# Satellite_Transceiver_Breakout__Swarm_M1.net
KiCad netlist of a schematic drawn in EAGLE
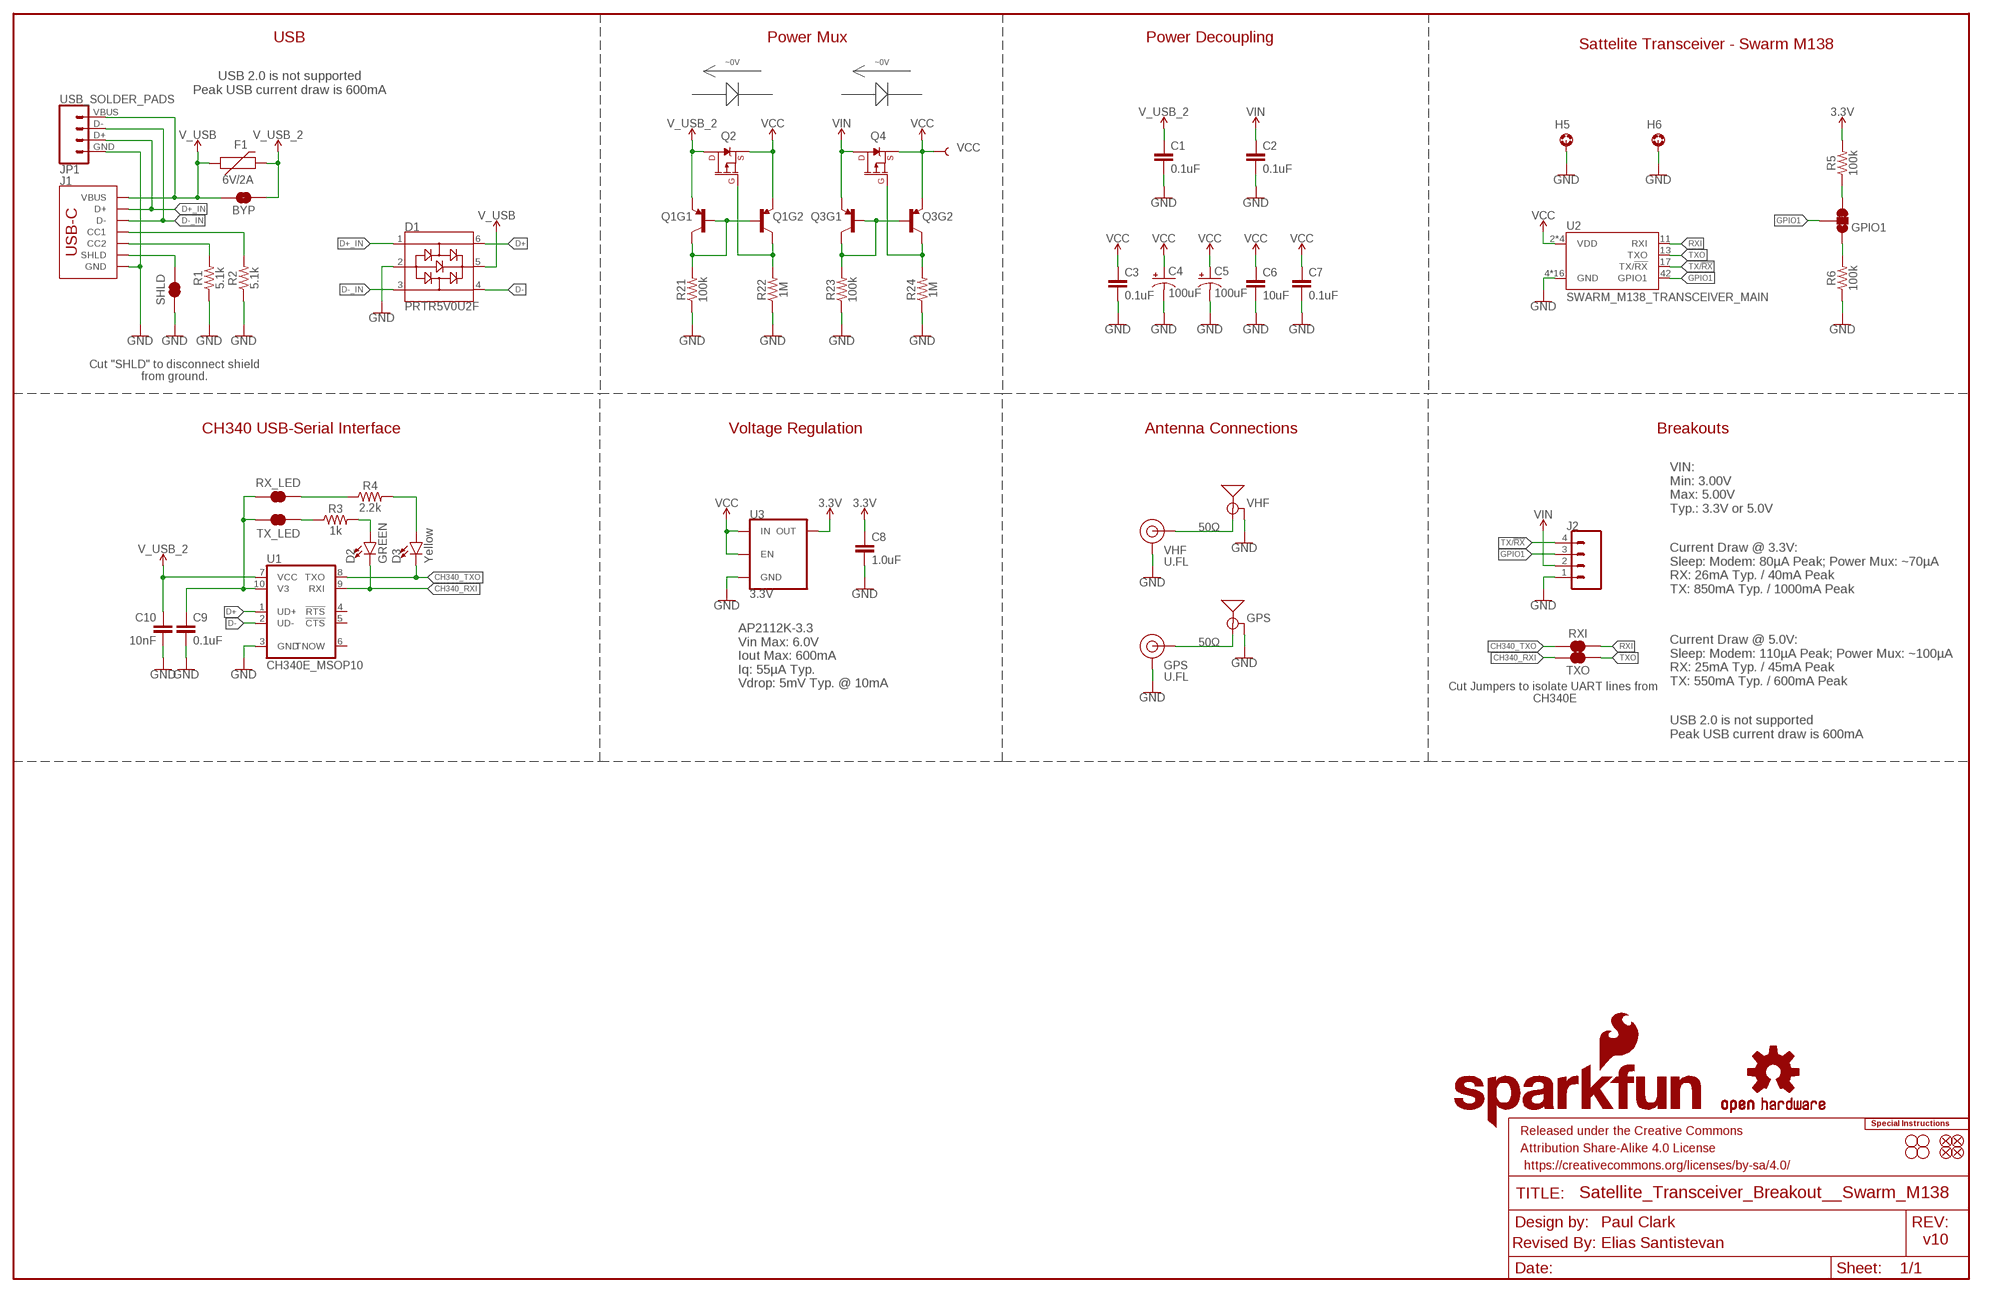
[diagram p0: schematic, sheet 1]

(export (version "E")
  (design (tool "Eeschema 10.0.6"))
  (components
    (comp (ref "BYP")
      (value "JUMPER-SMT_2_NO_SILK")
      (footprint "eagle-import:SMT-JUMPER_2_NO_SILK")
      (libsource (lib "eagle-import") (part "JUMPER-SMT_2_NO_SILK"))
    )
    (comp (ref "C1")
      (value "0.1uF")
      (footprint "eagle-import:0603")
      (libsource (lib "eagle-import") (part "0.1UF-0603-25V-5%"))
    )
    (comp (ref "C2")
      (value "0.1uF")
      (footprint "eagle-import:0603")
      (libsource (lib "eagle-import") (part "0.1UF-0603-25V-5%"))
    )
    (comp (ref "C3")
      (value "0.1uF")
      (footprint "eagle-import:0603")
      (libsource (lib "eagle-import") (part "0.1UF-0603-25V-5%"))
    )
    (comp (ref "C4")
      (value "100uF")
      (footprint "eagle-import:PANASONIC_D")
      (libsource (lib "eagle-import") (part "100UF-POLAR-25V-20%(ELEC)"))
    )
    (comp (ref "C5")
      (value "100uF")
      (footprint "eagle-import:PANASONIC_D")
      (libsource (lib "eagle-import") (part "100UF-POLAR-25V-20%(ELEC)"))
    )
    (comp (ref "C6")
      (value "10uF")
      (footprint "eagle-import:0603")
      (libsource (lib "eagle-import") (part "10UF-0603-6.3V-20%"))
    )
    (comp (ref "C7")
      (value "0.1uF")
      (footprint "eagle-import:0603")
      (libsource (lib "eagle-import") (part "0.1UF-0603-25V-5%"))
    )
    (comp (ref "C8")
      (value "1.0uF")
      (footprint "eagle-import:0603")
      (libsource (lib "eagle-import") (part "1.0UF-0603-16V-10%-X7R"))
    )
    (comp (ref "C9")
      (value "0.1uF")
      (footprint "eagle-import:0603")
      (libsource (lib "eagle-import") (part "0.1UF-0603-25V-5%"))
    )
    (comp (ref "C10")
      (value "10nF")
      (footprint "eagle-import:0603")
      (libsource (lib "eagle-import") (part "10NF-0603-50V-10%"))
    )
    (comp (ref "D1")
      (value "PRTR5V0U2F")
      (footprint "eagle-import:SOT886")
      (libsource (lib "eagle-import") (part "PRTR5V0U2F"))
    )
    (comp (ref "D2")
      (value "GREEN")
      (footprint "eagle-import:LED-0603")
      (libsource (lib "eagle-import") (part "LED-GREEN0603"))
    )
    (comp (ref "D3")
      (value "Yellow")
      (footprint "eagle-import:LED-0603")
      (libsource (lib "eagle-import") (part "LED-YELLOW0603"))
    )
    (comp (ref "E1")
      (value "VHF")
      (footprint "eagle-import:SMA-EDGE")
      (libsource (lib "eagle-import") (part "ANTENNA-SMA-GROUNDEDEDGE_SMA"))
    )
    (comp (ref "E2")
      (value "GPS")
      (footprint "eagle-import:SMA-EDGE")
      (libsource (lib "eagle-import") (part "ANTENNA-SMA-GROUNDEDEDGE_SMA"))
    )
    (comp (ref "F1")
      (value "6V/2A")
      (footprint "eagle-import:1210")
      (libsource (lib "eagle-import") (part "PPTC_6V2A"))
    )
    (comp (ref "FD1")
      (value "FIDUCIAL1X2")
      (footprint "eagle-import:FIDUCIAL-1X2")
      (libsource (lib "eagle-import") (part "FIDUCIAL1X2"))
    )
    (comp (ref "FD2")
      (value "FIDUCIAL1X2")
      (footprint "eagle-import:FIDUCIAL-1X2")
      (libsource (lib "eagle-import") (part "FIDUCIAL1X2"))
    )
    (comp (ref "FD3")
      (value "FIDUCIAL1X2")
      (footprint "eagle-import:FIDUCIAL-1X2")
      (libsource (lib "eagle-import") (part "FIDUCIAL1X2"))
    )
    (comp (ref "FD4")
      (value "FIDUCIAL1X2")
      (footprint "eagle-import:FIDUCIAL-1X2")
      (libsource (lib "eagle-import") (part "FIDUCIAL1X2"))
    )
    (comp (ref "FRAME1")
      (value "FRAME-LEDGER")
      (footprint "eagle-import:CREATIVE_COMMONS")
      (libsource (lib "eagle-import") (part "FRAME-LEDGER"))
    )
    (comp (ref "GPIO1")
      (value "JUMPER-SMT_3_1-NC_TRACE_SILK")
      (footprint "eagle-import:SMT-JUMPER_3_1-NC_TRACE_SILK")
      (libsource (lib "eagle-import") (part "JUMPER-SMT_3_1-NC_TRACE_SILK"))
    )
    (comp (ref "GPS")
      (value "U.FL")
      (footprint "eagle-import:U.FL")
      (libsource (lib "eagle-import") (part "U.FL2PIN"))
    )
    (comp (ref "H1")
      (value "STAND-OFF")
      (footprint "eagle-import:STAND-OFF")
      (libsource (lib "eagle-import") (part "STAND-OFF"))
    )
    (comp (ref "H2")
      (value "STAND-OFF")
      (footprint "eagle-import:STAND-OFF")
      (libsource (lib "eagle-import") (part "STAND-OFF"))
    )
    (comp (ref "H3")
      (value "STAND-OFF")
      (footprint "eagle-import:STAND-OFF")
      (libsource (lib "eagle-import") (part "STAND-OFF"))
    )
    (comp (ref "H4")
      (value "STAND-OFF")
      (footprint "eagle-import:STAND-OFF")
      (libsource (lib "eagle-import") (part "STAND-OFF"))
    )
    (comp (ref "H5")
      (value "STAND-OFF-REFLOW-M2.5_1.5MM_TALL")
      (footprint "eagle-import:STAND-OFF-REFLOW-M2.5")
      (libsource (lib "eagle-import") (part "STAND-OFF-REFLOW-M2.5_1.5MM_TALL"))
    )
    (comp (ref "H6")
      (value "STAND-OFF-REFLOW-M2.5_1.5MM_TALL")
      (footprint "eagle-import:STAND-OFF-REFLOW-M2.5")
      (libsource (lib "eagle-import") (part "STAND-OFF-REFLOW-M2.5_1.5MM_TALL"))
    )
    (comp (ref "J1")
      (value "USB_C_2-LAYER_PADS")
      (footprint "eagle-import:USB-C-16P-2LAYER-PADS")
      (libsource (lib "eagle-import") (part "USB_C_2-LAYER_PADS"))
    )
    (comp (ref "J2")
      (value "CONN_041X04_NO_SILK")
      (footprint "eagle-import:1X04_NO_SILK")
      (libsource (lib "eagle-import") (part "CONN_041X04_NO_SILK"))
    )
    (comp (ref "JP1")
      (value "USB_SOLDER_PADS")
      (footprint "eagle-import:USB-SOLDER-PADS")
      (libsource (lib "eagle-import") (part "USB_SOLDER_PADS"))
    )
    (comp (ref "LOGO1")
      (value "SPECIAL_INSTRUCTIONS-ORDERING")
      (footprint "eagle-import:ORDERING_INSTRUCTIONS")
      (libsource (lib "eagle-import") (part "SPECIAL_INSTRUCTIONS-ORDERING"))
    )
    (comp (ref "LOGO2")
      (value "OSHW-LOGOM")
      (footprint "eagle-import:OSHW-LOGO-M")
      (libsource (lib "eagle-import") (part "OSHW-LOGOM"))
    )
    (comp (ref "LOGO4")
      (value "SFE_LOGO_NAME_FLAME.1_INCH")
      (footprint "eagle-import:SFE_LOGO_NAME_FLAME_.1")
      (libsource (lib "eagle-import") (part "SFE_LOGO_NAME_FLAME.1_INCH"))
    )
    (comp (ref "Q1")
      (value "TRANS_PNP_DUALSOT-363")
      (footprint "eagle-import:SOT363_PHILIPS")
      (libsource (lib "eagle-import") (part "TRANS_PNP_DUALSOT-363"))
    )
    (comp (ref "Q2")
      (value "20V/4.2A/52mΩ/1.4W")
      (footprint "eagle-import:SOT23-3")
      (libsource (lib "eagle-import") (part "MOSFET_PCH-DMG2305UX-7"))
    )
    (comp (ref "Q3")
      (value "TRANS_PNP_DUALSOT-363")
      (footprint "eagle-import:SOT363_PHILIPS")
      (libsource (lib "eagle-import") (part "TRANS_PNP_DUALSOT-363"))
    )
    (comp (ref "Q4")
      (value "20V/4.2A/52mΩ/1.4W")
      (footprint "eagle-import:SOT23-3")
      (libsource (lib "eagle-import") (part "MOSFET_PCH-DMG2305UX-7"))
    )
    (comp (ref "R1")
      (value "5.1k")
      (footprint "eagle-import:0603")
      (libsource (lib "eagle-import") (part "5.1KOHM5.1KOHM-0603-1/10W-1%"))
    )
    (comp (ref "R2")
      (value "5.1k")
      (footprint "eagle-import:0603")
      (libsource (lib "eagle-import") (part "5.1KOHM5.1KOHM-0603-1/10W-1%"))
    )
    (comp (ref "R3")
      (value "1k")
      (footprint "eagle-import:0603")
      (libsource (lib "eagle-import") (part "1KOHM-0603-1/10W-1%"))
    )
    (comp (ref "R4")
      (value "2.2k")
      (footprint "eagle-import:0603")
      (libsource (lib "eagle-import") (part "2.2KOHM-0603-1/10W-1%"))
    )
    (comp (ref "R5")
      (value "100k")
      (footprint "eagle-import:0603")
      (libsource (lib "eagle-import") (part "100KOHM-0603-1/10W-1%"))
    )
    (comp (ref "R6")
      (value "100k")
      (footprint "eagle-import:0603")
      (libsource (lib "eagle-import") (part "100KOHM-0603-1/10W-1%"))
    )
    (comp (ref "R21")
      (value "100k")
      (footprint "eagle-import:0603")
      (libsource (lib "eagle-import") (part "100KOHM-0603-1/10W-1%"))
    )
    (comp (ref "R22")
      (value "1M")
      (footprint "eagle-import:0603")
      (libsource (lib "eagle-import") (part "1MOHM-0603-1/4W-5%"))
    )
    (comp (ref "R23")
      (value "100k")
      (footprint "eagle-import:0603")
      (libsource (lib "eagle-import") (part "100KOHM-0603-1/10W-1%"))
    )
    (comp (ref "R24")
      (value "1M")
      (footprint "eagle-import:0603")
      (libsource (lib "eagle-import") (part "1MOHM-0603-1/4W-5%"))
    )
    (comp (ref "RXI")
      (value "JUMPER-COMBO_2_NC_TRACE")
      (footprint "eagle-import:COMBO-JUMPER_2_NC_TRACE")
      (libsource (lib "eagle-import") (part "JUMPER-COMBO_2_NC_TRACE"))
    )
    (comp (ref "RX_LED")
      (value "JUMPER-SMT_2_NC_TRACE_SILK")
      (footprint "eagle-import:SMT-JUMPER_2_NC_TRACE_SILK")
      (libsource (lib "eagle-import") (part "JUMPER-SMT_2_NC_TRACE_SILK"))
    )
    (comp (ref "SHLD")
      (value "JUMPER-SMT_2_NC_TRACE_SILK")
      (footprint "eagle-import:SMT-JUMPER_2_NC_TRACE_SILK")
      (libsource (lib "eagle-import") (part "JUMPER-SMT_2_NC_TRACE_SILK"))
    )
    (comp (ref "TXO")
      (value "JUMPER-COMBO_2_NC_TRACE")
      (footprint "eagle-import:COMBO-JUMPER_2_NC_TRACE")
      (libsource (lib "eagle-import") (part "JUMPER-COMBO_2_NC_TRACE"))
    )
    (comp (ref "TX_LED")
      (value "JUMPER-SMT_2_NC_TRACE_SILK")
      (footprint "eagle-import:SMT-JUMPER_2_NC_TRACE_SILK")
      (libsource (lib "eagle-import") (part "JUMPER-SMT_2_NC_TRACE_SILK"))
    )
    (comp (ref "U1")
      (value "CH340E_MSOP10")
      (footprint "eagle-import:MSOP10")
      (libsource (lib "eagle-import") (part "CH340E_MSOP10"))
    )
    (comp (ref "U2")
      (value "SWARM_M138_TRANSCEIVER_MAIN")
      (footprint "eagle-import:M.2-SWARM-M138-A")
      (libsource (lib "eagle-import") (part "SWARM_M138_TRANSCEIVER_MAIN"))
    )
    (comp (ref "U3")
      (value "3.3V")
      (footprint "eagle-import:SOT23-5")
      (libsource (lib "eagle-import") (part "V_REG_AP2112K-3.3V"))
    )
    (comp (ref "VCC")
      (value "TEST-POINT3X5")
      (footprint "eagle-import:PAD.03X.05")
      (libsource (lib "eagle-import") (part "TEST-POINT3X5"))
    )
    (comp (ref "VHF")
      (value "U.FL")
      (footprint "eagle-import:U.FL")
      (libsource (lib "eagle-import") (part "U.FL2PIN"))
    )
  )
  (nets
    (net (code "1") (name "/TX{slash}~{RX}") (class "Default")
      (node (ref "J2") (pin "4") (pinfunction "4_4") (pintype "passive"))
      (node (ref "U2") (pin "17") (pinfunction "TX/~{RX}_17") (pintype "output"))
    )
    (net (code "2") (name "3.3V") (class "Default")
      (node (ref "C8") (pin "1") (pinfunction "1_1") (pintype "passive"))
      (node (ref "R5") (pin "2") (pinfunction "2_2") (pintype "passive"))
      (node (ref "U3") (pin "5") (pinfunction "OUT_5") (pintype "passive"))
    )
    (net (code "3") (name "CH340_RXI") (class "Default")
      (node (ref "D2") (pin "C") (pinfunction "C_C") (pintype "passive"))
      (node (ref "TXO") (pin "2") (pinfunction "2_2") (pintype "passive"))
      (node (ref "TXO") (pin "4") (pinfunction "2_4") (pintype "passive"))
      (node (ref "U1") (pin "9") (pinfunction "RXI_9") (pintype "bidirectional"))
    )
    (net (code "4") (name "CH340_TXO") (class "Default")
      (node (ref "D3") (pin "C") (pinfunction "C_C") (pintype "passive"))
      (node (ref "RXI") (pin "1") (pinfunction "1_1") (pintype "passive"))
      (node (ref "RXI") (pin "3") (pinfunction "1_3") (pintype "passive"))
      (node (ref "U1") (pin "8") (pinfunction "TXO_8") (pintype "bidirectional"))
    )
    (net (code "5") (name "D+") (class "Default")
      (node (ref "D1") (pin "6") (pinfunction "6_6") (pintype "bidirectional"))
      (node (ref "U1") (pin "1") (pinfunction "UD+_1") (pintype "bidirectional"))
    )
    (net (code "6") (name "D+_IN") (class "Default")
      (node (ref "D1") (pin "1") (pinfunction "1_1") (pintype "bidirectional"))
      (node (ref "J1") (pin "A6") (pinfunction "D+_A6") (pintype "bidirectional"))
      (node (ref "J1") (pin "B6") (pinfunction "D+_B6") (pintype "bidirectional"))
      (node (ref "JP1") (pin "D+") (pinfunction "3_D+") (pintype "passive"))
    )
    (net (code "7") (name "D-") (class "Default")
      (node (ref "D1") (pin "4") (pinfunction "4_4") (pintype "bidirectional"))
      (node (ref "U1") (pin "2") (pinfunction "UD-_2") (pintype "bidirectional"))
    )
    (net (code "8") (name "D-_IN") (class "Default")
      (node (ref "D1") (pin "3") (pinfunction "3_3") (pintype "bidirectional"))
      (node (ref "J1") (pin "A7") (pinfunction "D-_A7") (pintype "bidirectional"))
      (node (ref "J1") (pin "B7") (pinfunction "D-_B7") (pintype "bidirectional"))
      (node (ref "JP1") (pin "D-") (pinfunction "2_D-") (pintype "passive"))
    )
    (net (code "9") (name "GND") (class "Default")
      (node (ref "C1") (pin "2") (pinfunction "2_2") (pintype "passive"))
      (node (ref "C10") (pin "2") (pinfunction "2_2") (pintype "passive"))
      (node (ref "C2") (pin "2") (pinfunction "2_2") (pintype "passive"))
      (node (ref "C3") (pin "2") (pinfunction "2_2") (pintype "passive"))
      (node (ref "C4") (pin "-") (pinfunction "-_-") (pintype "passive"))
      (node (ref "C5") (pin "-") (pinfunction "-_-") (pintype "passive"))
      (node (ref "C6") (pin "2") (pinfunction "2_2") (pintype "passive"))
      (node (ref "C7") (pin "2") (pinfunction "2_2") (pintype "passive"))
      (node (ref "C8") (pin "2") (pinfunction "2_2") (pintype "passive"))
      (node (ref "C9") (pin "2") (pinfunction "2_2") (pintype "passive"))
      (node (ref "D1") (pin "2") (pinfunction "2_2") (pintype "power_in"))
      (node (ref "E1") (pin "GND@0") (pinfunction "GND_GND@0") (pintype "bidirectional"))
      (node (ref "E1") (pin "GND@1") (pinfunction "GND_GND@1") (pintype "bidirectional"))
      (node (ref "E1") (pin "GND@2") (pinfunction "GND_GND@2") (pintype "bidirectional"))
      (node (ref "E1") (pin "GND@3") (pinfunction "GND_GND@3") (pintype "bidirectional"))
      (node (ref "E2") (pin "GND@0") (pinfunction "GND_GND@0") (pintype "bidirectional"))
      (node (ref "E2") (pin "GND@1") (pinfunction "GND_GND@1") (pintype "bidirectional"))
      (node (ref "E2") (pin "GND@2") (pinfunction "GND_GND@2") (pintype "bidirectional"))
      (node (ref "E2") (pin "GND@3") (pinfunction "GND_GND@3") (pintype "bidirectional"))
      (node (ref "GPS") (pin "1") (pinfunction "GND_1") (pintype "bidirectional"))
      (node (ref "GPS") (pin "2") (pinfunction "GND_2") (pintype "bidirectional"))
      (node (ref "H5") (pin "1") (pinfunction "1_1") (pintype "bidirectional"))
      (node (ref "H6") (pin "1") (pinfunction "1_1") (pintype "bidirectional"))
      (node (ref "J1") (pin "GND") (pinfunction "GND_GND") (pintype "bidirectional"))
      (node (ref "J1") (pin "GND2") (pinfunction "GND_GND2") (pintype "bidirectional"))
      (node (ref "J2") (pin "1") (pinfunction "1_1") (pintype "passive"))
      (node (ref "JP1") (pin "GND") (pinfunction "4_GND") (pintype "passive"))
      (node (ref "R1") (pin "1") (pinfunction "1_1") (pintype "passive"))
      (node (ref "R2") (pin "1") (pinfunction "1_1") (pintype "passive"))
      (node (ref "R21") (pin "1") (pinfunction "1_1") (pintype "passive"))
      (node (ref "R22") (pin "1") (pinfunction "1_1") (pintype "passive"))
      (node (ref "R23") (pin "1") (pinfunction "1_1") (pintype "passive"))
      (node (ref "R24") (pin "1") (pinfunction "1_1") (pintype "passive"))
      (node (ref "R6") (pin "1") (pinfunction "1_1") (pintype "passive"))
      (node (ref "SHLD") (pin "1") (pinfunction "1_1") (pintype "passive"))
      (node (ref "U1") (pin "3") (pinfunction "GND_3") (pintype "bidirectional"))
      (node (ref "U2") (pin "15") (pinfunction "GND_15") (pintype "power_in"))
      (node (ref "U2") (pin "18") (pinfunction "GND_18") (pintype "power_in"))
      (node (ref "U2") (pin "21") (pinfunction "GND_21") (pintype "power_in"))
      (node (ref "U2") (pin "26") (pinfunction "GND_26") (pintype "power_in"))
      (node (ref "U2") (pin "27") (pinfunction "GND_27") (pintype "power_in"))
      (node (ref "U2") (pin "29") (pinfunction "GND_29") (pintype "power_in"))
      (node (ref "U2") (pin "34") (pinfunction "GND_34") (pintype "power_in"))
      (node (ref "U2") (pin "35") (pinfunction "GND_35") (pintype "power_in"))
      (node (ref "U2") (pin "37") (pinfunction "GND_37") (pintype "power_in"))
      (node (ref "U2") (pin "4") (pinfunction "GND_4") (pintype "power_in"))
      (node (ref "U2") (pin "40") (pinfunction "GND_40") (pintype "power_in"))
      (node (ref "U2") (pin "43") (pinfunction "GND_43") (pintype "power_in"))
      (node (ref "U2") (pin "50") (pinfunction "GND_50") (pintype "power_in"))
      (node (ref "U2") (pin "9") (pinfunction "GND_9") (pintype "power_in"))
      (node (ref "U2") (pin "A1") (pinfunction "GND_A1") (pintype "power_in"))
      (node (ref "U2") (pin "A2") (pinfunction "GND_A2") (pintype "power_in"))
      (node (ref "U3") (pin "2") (pinfunction "GND_2") (pintype "input"))
      (node (ref "VHF") (pin "1") (pinfunction "GND_1") (pintype "bidirectional"))
      (node (ref "VHF") (pin "2") (pinfunction "GND_2") (pintype "bidirectional"))
    )
    (net (code "10") (name "GPIO1") (class "Default")
      (node (ref "GPIO1") (pin "2") (pinfunction "2_2") (pintype "passive"))
      (node (ref "J2") (pin "3") (pinfunction "3_3") (pintype "passive"))
      (node (ref "U2") (pin "42") (pinfunction "GPIO1_42") (pintype "bidirectional"))
    )
    (net (code "11") (name "Net-(D2-PadA)") (class "Default")
      (node (ref "D2") (pin "A") (pinfunction "A_A") (pintype "passive"))
      (node (ref "R3") (pin "2") (pinfunction "2_2") (pintype "passive"))
    )
    (net (code "12") (name "Net-(D3-PadA)") (class "Default")
      (node (ref "D3") (pin "A") (pinfunction "A_A") (pintype "passive"))
      (node (ref "R4") (pin "2") (pinfunction "2_2") (pintype "passive"))
    )
    (net (code "13") (name "Net-(E1-SIGNAL)") (class "Default")
      (node (ref "E1") (pin "SIG") (pinfunction "SIGNAL_SIG") (pintype "bidirectional"))
      (node (ref "VHF") (pin "FEED") (pinfunction "SIGNAL_FEED") (pintype "bidirectional"))
    )
    (net (code "14") (name "Net-(E2-SIGNAL)") (class "Default")
      (node (ref "E2") (pin "SIG") (pinfunction "SIGNAL_SIG") (pintype "bidirectional"))
      (node (ref "GPS") (pin "FEED") (pinfunction "SIGNAL_FEED") (pintype "bidirectional"))
    )
    (net (code "15") (name "Net-(GPIO1-Pad1)") (class "Default")
      (node (ref "GPIO1") (pin "1") (pinfunction "1_1") (pintype "passive"))
      (node (ref "R6") (pin "2") (pinfunction "2_2") (pintype "passive"))
    )
    (net (code "16") (name "Net-(GPIO1-Pad3)") (class "Default")
      (node (ref "GPIO1") (pin "3") (pinfunction "3_3") (pintype "passive"))
      (node (ref "R5") (pin "1") (pinfunction "1_1") (pintype "passive"))
    )
    (net (code "17") (name "Net-(J1-CC1)") (class "Default")
      (node (ref "J1") (pin "A5") (pinfunction "CC1_A5") (pintype "bidirectional"))
      (node (ref "R2") (pin "2") (pinfunction "2_2") (pintype "passive"))
    )
    (net (code "18") (name "Net-(J1-CC2)") (class "Default")
      (node (ref "J1") (pin "B5") (pinfunction "CC2_B5") (pintype "bidirectional"))
      (node (ref "R1") (pin "2") (pinfunction "2_2") (pintype "passive"))
    )
    (net (code "19") (name "Net-(J1-SHLD-PadSHLD1)") (class "Default")
      (node (ref "J1") (pin "SHLD1") (pinfunction "SHLD_SHLD1") (pintype "bidirectional"))
      (node (ref "J1") (pin "SHLD2") (pinfunction "SHLD_SHLD2") (pintype "bidirectional"))
      (node (ref "J1") (pin "SHLD3") (pinfunction "SHLD_SHLD3") (pintype "bidirectional"))
      (node (ref "J1") (pin "SHLD4") (pinfunction "SHLD_SHLD4") (pintype "bidirectional"))
      (node (ref "SHLD") (pin "2") (pinfunction "2_2") (pintype "passive"))
    )
    (net (code "20") (name "Net-(Q1A-B)") (class "Default")
      (node (ref "Q1") (pin "2") (pinfunction "B_2") (pintype "passive"))
      (node (ref "Q1") (pin "5") (pinfunction "B_5") (pintype "passive"))
      (node (ref "Q1") (pin "6") (pinfunction "C_6") (pintype "passive"))
      (node (ref "R21") (pin "2") (pinfunction "2_2") (pintype "passive"))
    )
    (net (code "21") (name "Net-(Q1B-C)") (class "Default")
      (node (ref "Q1") (pin "3") (pinfunction "C_3") (pintype "passive"))
      (node (ref "Q2") (pin "1") (pinfunction "G_1") (pintype "bidirectional"))
      (node (ref "R22") (pin "2") (pinfunction "2_2") (pintype "passive"))
    )
    (net (code "22") (name "Net-(Q3A-B)") (class "Default")
      (node (ref "Q3") (pin "2") (pinfunction "B_2") (pintype "passive"))
      (node (ref "Q3") (pin "5") (pinfunction "B_5") (pintype "passive"))
      (node (ref "Q3") (pin "6") (pinfunction "C_6") (pintype "passive"))
      (node (ref "R23") (pin "2") (pinfunction "2_2") (pintype "passive"))
    )
    (net (code "23") (name "Net-(Q3B-C)") (class "Default")
      (node (ref "Q3") (pin "3") (pinfunction "C_3") (pintype "passive"))
      (node (ref "Q4") (pin "1") (pinfunction "G_1") (pintype "bidirectional"))
      (node (ref "R24") (pin "2") (pinfunction "2_2") (pintype "passive"))
    )
    (net (code "24") (name "Net-(R3-Pad1)") (class "Default")
      (node (ref "R3") (pin "1") (pinfunction "1_1") (pintype "passive"))
      (node (ref "TX_LED") (pin "1") (pinfunction "1_1") (pintype "passive"))
    )
    (net (code "25") (name "Net-(R4-Pad1)") (class "Default")
      (node (ref "R4") (pin "1") (pinfunction "1_1") (pintype "passive"))
      (node (ref "RX_LED") (pin "2") (pinfunction "2_2") (pintype "passive"))
    )
    (net (code "26") (name "Net-(U1-V3)") (class "Default")
      (node (ref "C9") (pin "1") (pinfunction "1_1") (pintype "passive"))
      (node (ref "RX_LED") (pin "1") (pinfunction "1_1") (pintype "passive"))
      (node (ref "TX_LED") (pin "2") (pinfunction "2_2") (pintype "passive"))
      (node (ref "U1") (pin "10") (pinfunction "V3_10") (pintype "bidirectional"))
    )
    (net (code "27") (name "RXI") (class "Default")
      (node (ref "RXI") (pin "2") (pinfunction "2_2") (pintype "passive"))
      (node (ref "RXI") (pin "4") (pinfunction "2_4") (pintype "passive"))
      (node (ref "U2") (pin "11") (pinfunction "RXI_11") (pintype "input"))
    )
    (net (code "28") (name "TXO") (class "Default")
      (node (ref "TXO") (pin "1") (pinfunction "1_1") (pintype "passive"))
      (node (ref "TXO") (pin "3") (pinfunction "1_3") (pintype "passive"))
      (node (ref "U2") (pin "13") (pinfunction "TXO_13") (pintype "output"))
    )
    (net (code "29") (name "VCC") (class "Default")
      (node (ref "C3") (pin "1") (pinfunction "1_1") (pintype "passive"))
      (node (ref "C4") (pin "+") (pinfunction "+_+") (pintype "passive"))
      (node (ref "C5") (pin "+") (pinfunction "+_+") (pintype "passive"))
      (node (ref "C6") (pin "1") (pinfunction "1_1") (pintype "passive"))
      (node (ref "C7") (pin "1") (pinfunction "1_1") (pintype "passive"))
      (node (ref "Q1") (pin "4") (pinfunction "E_4") (pintype "passive"))
      (node (ref "Q2") (pin "2") (pinfunction "S_2") (pintype "bidirectional"))
      (node (ref "Q3") (pin "4") (pinfunction "E_4") (pintype "passive"))
      (node (ref "Q4") (pin "2") (pinfunction "S_2") (pintype "bidirectional"))
      (node (ref "U2") (pin "2") (pinfunction "VDD_2") (pintype "power_in"))
      (node (ref "U2") (pin "39") (pinfunction "VDD_39") (pintype "power_in"))
      (node (ref "U2") (pin "41") (pinfunction "VDD_41") (pintype "power_in"))
      (node (ref "U2") (pin "52") (pinfunction "VDD_52") (pintype "power_in"))
      (node (ref "U3") (pin "1") (pinfunction "IN_1") (pintype "input"))
      (node (ref "U3") (pin "3") (pinfunction "EN_3") (pintype "input"))
      (node (ref "VCC") (pin "1") (pinfunction "1_1") (pintype "bidirectional"))
    )
    (net (code "30") (name "VIN") (class "Default")
      (node (ref "C2") (pin "1") (pinfunction "1_1") (pintype "passive"))
      (node (ref "J2") (pin "2") (pinfunction "2_2") (pintype "passive"))
      (node (ref "Q3") (pin "1") (pinfunction "E_1") (pintype "passive"))
      (node (ref "Q4") (pin "3") (pinfunction "D_3") (pintype "bidirectional"))
    )
    (net (code "31") (name "V_USB") (class "Default")
      (node (ref "BYP") (pin "2") (pinfunction "2_2") (pintype "passive"))
      (node (ref "D1") (pin "5") (pinfunction "5_5") (pintype "power_in"))
      (node (ref "F1") (pin "1") (pinfunction "1_1") (pintype "bidirectional"))
      (node (ref "J1") (pin "VBUS1") (pinfunction "VBUS_VBUS1") (pintype "bidirectional"))
      (node (ref "J1") (pin "VBUS2") (pinfunction "VBUS_VBUS2") (pintype "bidirectional"))
      (node (ref "JP1") (pin "VBUS") (pinfunction "1_VBUS") (pintype "passive"))
    )
    (net (code "32") (name "V_USB_2") (class "Default")
      (node (ref "BYP") (pin "1") (pinfunction "1_1") (pintype "passive"))
      (node (ref "C1") (pin "1") (pinfunction "1_1") (pintype "passive"))
      (node (ref "C10") (pin "1") (pinfunction "1_1") (pintype "passive"))
      (node (ref "F1") (pin "2") (pinfunction "2_2") (pintype "bidirectional"))
      (node (ref "Q1") (pin "1") (pinfunction "E_1") (pintype "passive"))
      (node (ref "Q2") (pin "3") (pinfunction "D_3") (pintype "bidirectional"))
      (node (ref "U1") (pin "7") (pinfunction "VCC_7") (pintype "bidirectional"))
    )
    (net (code "33") (name "unconnected-(U1-TNOW-Pad6)") (class "Default")
      (node (ref "U1") (pin "6") (pinfunction "TNOW_6") (pintype "bidirectional"))
    )
    (net (code "34") (name "unconnected-(U1-~{CTS}-Pad5)") (class "Default")
      (node (ref "U1") (pin "5") (pinfunction "~{CTS}_5") (pintype "bidirectional"))
    )
    (net (code "35") (name "unconnected-(U1-~{RTS}-Pad4)") (class "Default")
      (node (ref "U1") (pin "4") (pinfunction "~{RTS}_4") (pintype "bidirectional"))
    )
  )
)
